# Sheet1.net
KiCad netlist of a schematic drawn in Altium Designer
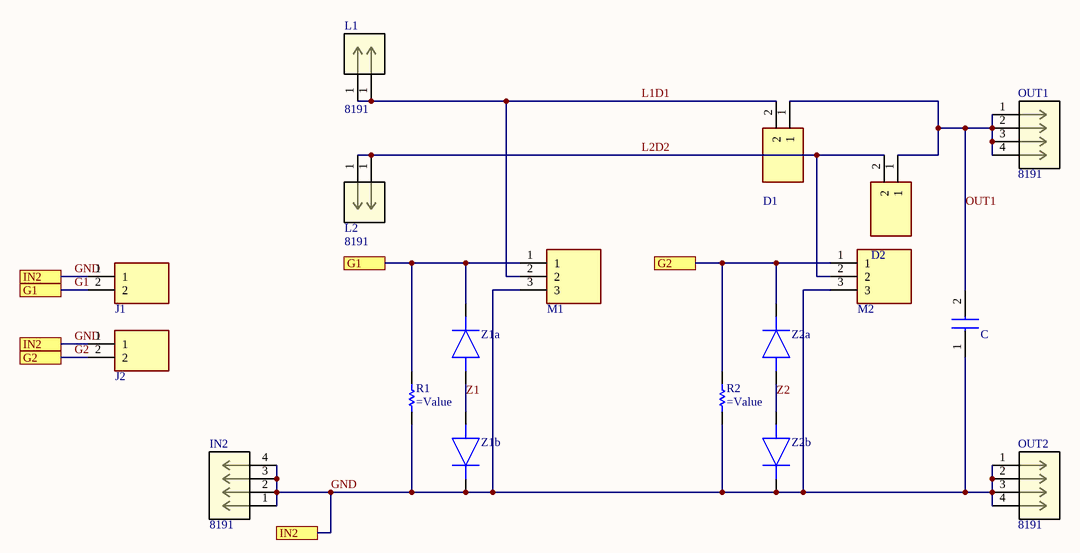
[diagram p0: Sheet1.SchDoc]

(export (version "E")
  (design (tool "Eeschema 10.0.6"))
  (components
    (comp (ref "C")
      (value "CAP")
      (footprint "Capacitor")
      (description "Capacitor")
      (fields
        (field (name "MANUFACTURER_PART_NUMBER") "C1206X475K3RACAUTO7210")
        (field (name "MOUSER PART NUMBER") "80-C1206X475K3RAUTLR")
      )
      (libsource (lib "Schlib1") (part "CAP"))
    )
    (comp (ref "D1")
      (value "TB004-508-02BE")
      (footprint "TERMINAL_CIN_TH_2P_5.08")
      (description "Connector")
      (fields (field (name "MOUSER PART NUMBER") "490-TB004-508-02BE"))
      (libsource (lib "Integrated_Library_GEPE") (part "Con_Terminal_2P"))
    )
    (comp (ref "D2")
      (value "TB004-508-02BE")
      (footprint "TERMINAL_CIN_TH_2P_5.08")
      (description "Connector")
      (fields (field (name "MOUSER PART NUMBER") "490-TB004-508-02BE"))
      (libsource (lib "Integrated_Library_GEPE") (part "Con_Terminal_2P"))
    )
    (comp (ref "IN2")
      (value "8191")
      (footprint "CONN_8191_KEY")
      (description "No Description Available")
      (fields (field (name "COPYRIGHT") "Copyright (C) 2022 Ultra Librarian. All rights reserved."))
      (libsource (lib "") (part "8191_1"))
    )
    (comp (ref "J1")
      (value "TB004-508-02BE")
      (footprint "HEADER_MALE_TH_2P_2.54")
      (description "Connector")
      (fields (field (name "MOUSER PART NUMBER") "490-TB004-508-02BE"))
      (libsource (lib "Integrated_Library_GEPE") (part "Con_Header_2P"))
    )
    (comp (ref "J2")
      (value "TB004-508-02BE")
      (footprint "HEADER_MALE_TH_2P_2.54")
      (description "Connector")
      (fields (field (name "MOUSER PART NUMBER") "490-TB004-508-02BE"))
      (libsource (lib "Integrated_Library_GEPE") (part "Con_Header_2P"))
    )
    (comp (ref "L1")
      (value "8191")
      (footprint "TermIND")
      (description "No Description Available")
      (fields (field (name "COPYRIGHT") "Copyright (C) 2022 Ultra Librarian. All rights reserved."))
      (libsource (lib "Schlib1") (part "2Pins"))
    )
    (comp (ref "L2")
      (value "8191")
      (footprint "TermIND")
      (description "No Description Available")
      (fields (field (name "COPYRIGHT") "Copyright (C) 2022 Ultra Librarian. All rights reserved."))
      (libsource (lib "") (part "2Pins_1"))
    )
    (comp (ref "M1")
      (value "1546551-3")
      (footprint "TERMINAL_TH_3P_5.08")
      (description "Terminal")
      (fields (field (name "MOUSER PART NUMBER") "571-1546551-3"))
      (libsource (lib "Integrated_Library_GEPE") (part "Con_Terminal_3P"))
    )
    (comp (ref "M2")
      (value "1546551-3")
      (footprint "TERMINAL_TH_3P_5.08")
      (description "Terminal")
      (fields (field (name "MOUSER PART NUMBER") "571-1546551-3"))
      (libsource (lib "Integrated_Library_GEPE") (part "Con_Terminal_3P"))
    )
    (comp (ref "OUT1")
      (value "8191")
      (footprint "CONN_8191_KEY")
      (description "No Description Available")
      (fields (field (name "COPYRIGHT") "Copyright (C) 2022 Ultra Librarian. All rights reserved."))
      (libsource (lib "Schlib1") (part "8191"))
    )
    (comp (ref "OUT2")
      (value "8191")
      (footprint "CONN_8191_KEY")
      (description "No Description Available")
      (fields (field (name "COPYRIGHT") "Copyright (C) 2022 Ultra Librarian. All rights reserved."))
      (libsource (lib "Schlib1") (part "8191"))
    )
    (comp (ref "R1")
      (value "Res1")
      (footprint "RESIS_TH_10.1")
      (description "Resistor")
      (fields (field (name "PUBLISHER") "Altium Limited"))
      (libsource (lib "Integrated_Library_GEPE") (part "Resistor"))
    )
    (comp (ref "R2")
      (value "Res1")
      (footprint "RESIS_TH_10.1")
      (description "Resistor")
      (fields (field (name "PUBLISHER") "Altium Limited"))
      (libsource (lib "Integrated_Library_GEPE") (part "Resistor"))
    )
    (comp (ref "Z1a")
      (value "TLHR5400-AS12Z")
      (footprint "DIODE_TH_10.1")
      (description "Diode")
      (libsource (lib "Integrated_Library_GEPE") (part "Diode"))
    )
    (comp (ref "Z1b")
      (value "TLHR5400-AS12Z")
      (footprint "DIODE_TH_10.1")
      (description "Diode")
      (libsource (lib "Integrated_Library_GEPE") (part "Diode"))
    )
    (comp (ref "Z2a")
      (value "TLHR5400-AS12Z")
      (footprint "DIODE_TH_10.1")
      (description "Diode")
      (libsource (lib "Integrated_Library_GEPE") (part "Diode"))
    )
    (comp (ref "Z2b")
      (value "TLHR5400-AS12Z")
      (footprint "DIODE_TH_10.1")
      (description "Diode")
      (libsource (lib "Integrated_Library_GEPE") (part "Diode"))
    )
  )
  (nets
    (net (code "1") (name "/G1") (class "Default")
      (node (ref "J1") (pin "2") (pinfunction "2_2") (pintype "passive"))
      (node (ref "M1") (pin "1") (pinfunction "1_1") (pintype "passive"))
      (node (ref "R1") (pin "2") (pinfunction "2_2") (pintype "passive"))
      (node (ref "Z1a") (pin "1") (pinfunction "K_1") (pintype "passive"))
    )
    (net (code "2") (name "/G2") (class "Default")
      (node (ref "J2") (pin "2") (pinfunction "2_2") (pintype "passive"))
      (node (ref "M2") (pin "1") (pinfunction "1_1") (pintype "passive"))
      (node (ref "R2") (pin "2") (pinfunction "2_2") (pintype "passive"))
      (node (ref "Z2a") (pin "1") (pinfunction "K_1") (pintype "passive"))
    )
    (net (code "3") (name "/GND") (class "Default")
      (node (ref "C") (pin "1") (pinfunction "1_1") (pintype "passive"))
      (node (ref "IN2") (pin "1") (pinfunction "1_1") (pintype "passive"))
      (node (ref "IN2") (pin "2") (pinfunction "2_2") (pintype "passive"))
      (node (ref "IN2") (pin "3") (pinfunction "3_3") (pintype "passive"))
      (node (ref "IN2") (pin "4") (pinfunction "4_4") (pintype "passive"))
      (node (ref "J1") (pin "1") (pinfunction "1_1") (pintype "passive"))
      (node (ref "J2") (pin "1") (pinfunction "1_1") (pintype "passive"))
      (node (ref "M1") (pin "3") (pinfunction "3_3") (pintype "passive"))
      (node (ref "M2") (pin "3") (pinfunction "3_3") (pintype "passive"))
      (node (ref "OUT2") (pin "1") (pinfunction "1_1") (pintype "passive"))
      (node (ref "OUT2") (pin "2") (pinfunction "2_2") (pintype "passive"))
      (node (ref "OUT2") (pin "3") (pinfunction "3_3") (pintype "passive"))
      (node (ref "OUT2") (pin "4") (pinfunction "4_4") (pintype "passive"))
      (node (ref "R1") (pin "1") (pinfunction "1_1") (pintype "passive"))
      (node (ref "R2") (pin "1") (pinfunction "1_1") (pintype "passive"))
      (node (ref "Z1b") (pin "1") (pinfunction "K_1") (pintype "passive"))
      (node (ref "Z2b") (pin "1") (pinfunction "K_1") (pintype "passive"))
    )
    (net (code "4") (name "/L1D1") (class "Default")
      (node (ref "D1") (pin "2") (pinfunction "2_2") (pintype "passive"))
      (node (ref "L1") (pin "1") (pinfunction "1_1") (pintype "passive"))
      (node (ref "M1") (pin "2") (pinfunction "2_2") (pintype "passive"))
    )
    (net (code "5") (name "/L2D2") (class "Default")
      (node (ref "D2") (pin "2") (pinfunction "2_2") (pintype "passive"))
      (node (ref "L2") (pin "1") (pinfunction "1_1") (pintype "passive"))
      (node (ref "M2") (pin "2") (pinfunction "2_2") (pintype "passive"))
    )
    (net (code "6") (name "/OUT1") (class "Default")
      (node (ref "C") (pin "2") (pinfunction "2_2") (pintype "passive"))
      (node (ref "D1") (pin "1") (pinfunction "1_1") (pintype "passive"))
      (node (ref "D2") (pin "1") (pinfunction "1_1") (pintype "passive"))
      (node (ref "OUT1") (pin "1") (pinfunction "1_1") (pintype "passive"))
      (node (ref "OUT1") (pin "2") (pinfunction "2_2") (pintype "passive"))
      (node (ref "OUT1") (pin "3") (pinfunction "3_3") (pintype "passive"))
      (node (ref "OUT1") (pin "4") (pinfunction "4_4") (pintype "passive"))
    )
    (net (code "7") (name "/Z1") (class "Default")
      (node (ref "Z1a") (pin "2") (pinfunction "A_2") (pintype "passive"))
      (node (ref "Z1b") (pin "2") (pinfunction "A_2") (pintype "passive"))
    )
    (net (code "8") (name "/Z2") (class "Default")
      (node (ref "Z2a") (pin "2") (pinfunction "A_2") (pintype "passive"))
      (node (ref "Z2b") (pin "2") (pinfunction "A_2") (pintype "passive"))
    )
  )
)
